# lab1.net
KiCad netlist of a schematic drawn in EAGLE
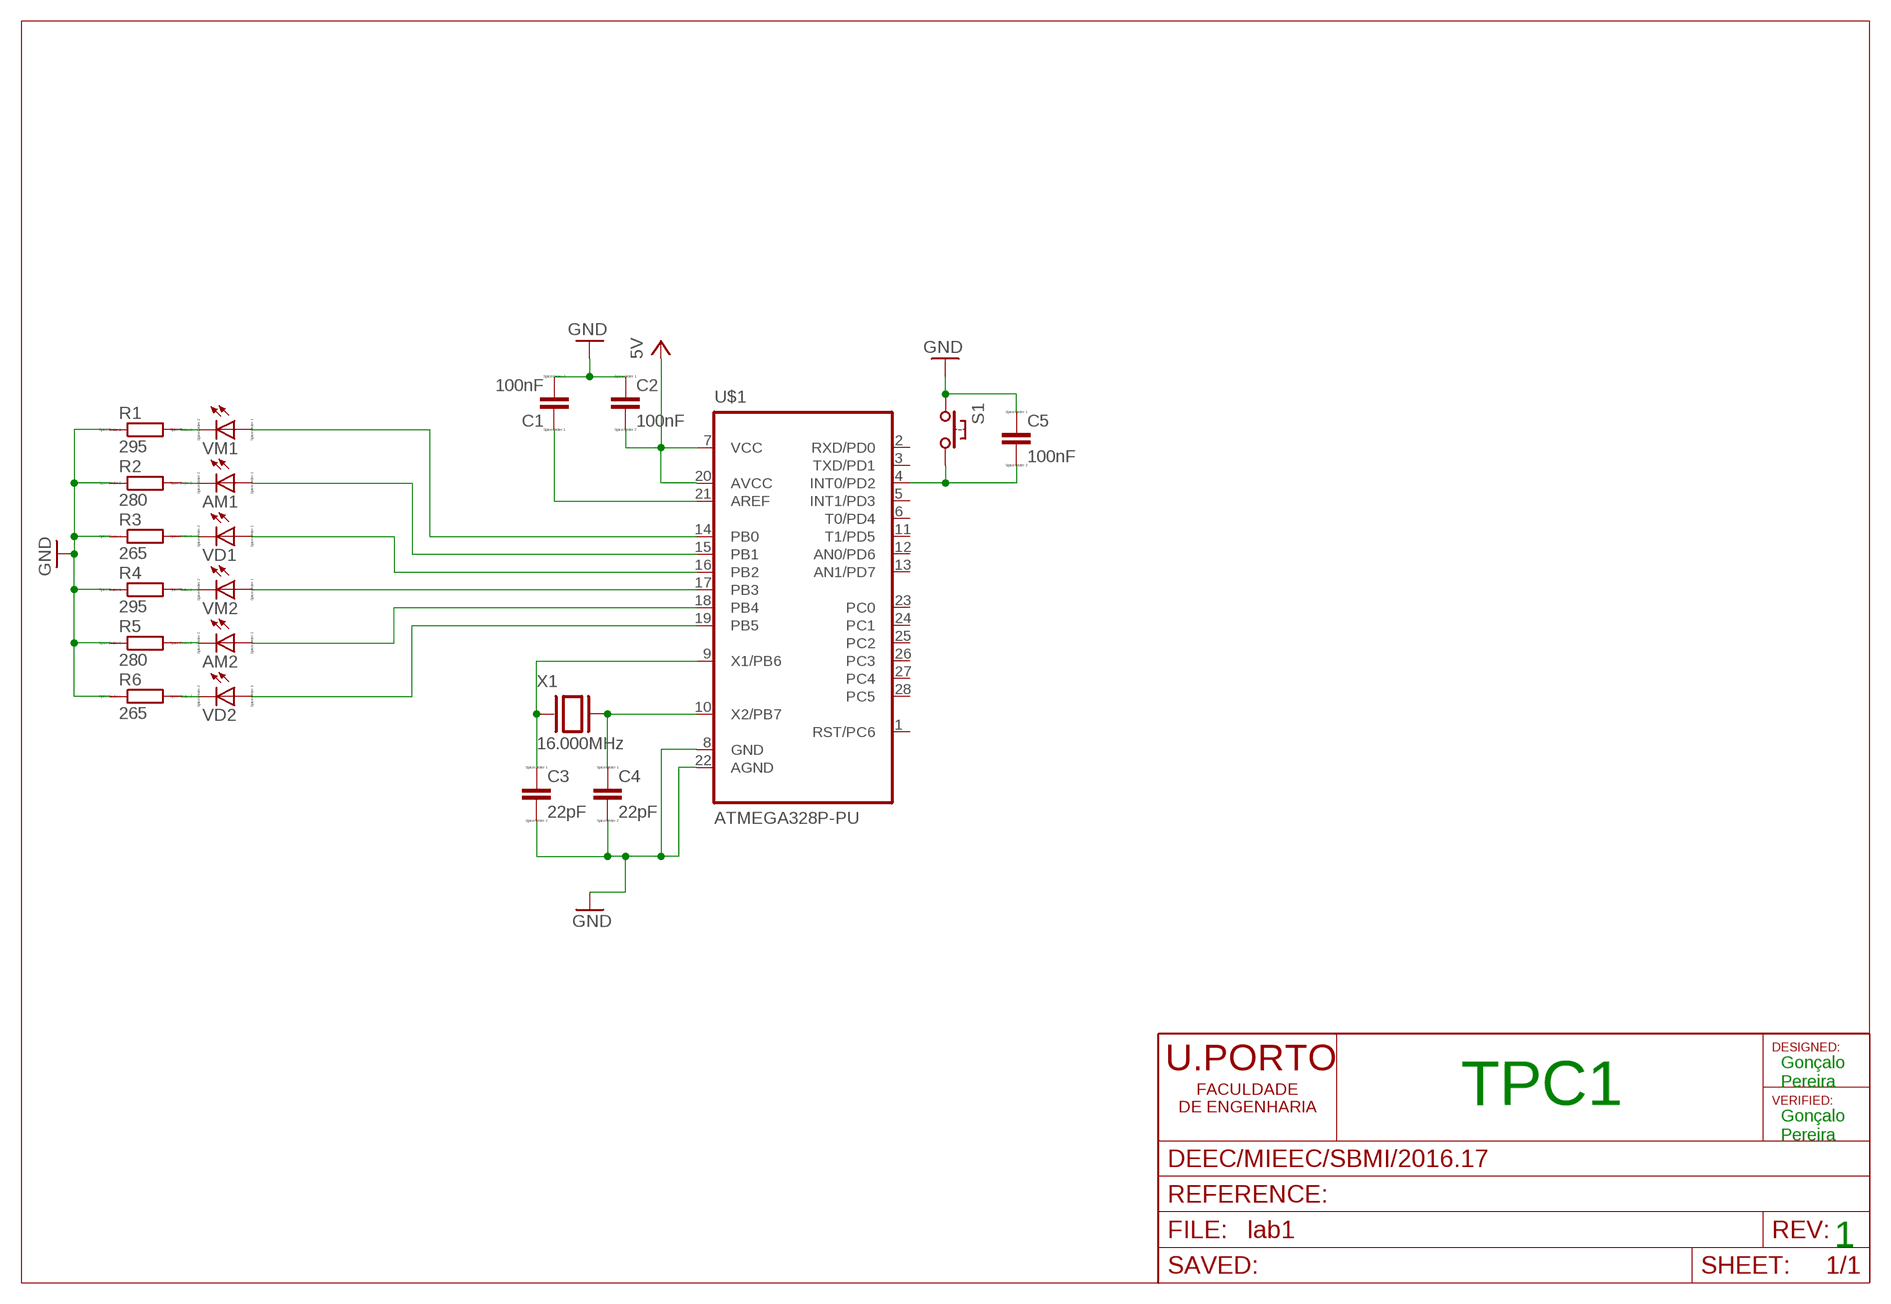
[diagram p0: schematic, sheet 1]

(export (version "E")
  (design (tool "Eeschema 10.0.6"))
  (components
    (comp (ref "AM1")
      (value "LED_ELD260")
      (footprint "eagle-import:LED_LD260")
      (libsource (lib "eagle-import") (part "LED_ELD260"))
    )
    (comp (ref "AM2")
      (value "LED_ELD260")
      (footprint "eagle-import:LED_LD260")
      (libsource (lib "eagle-import") (part "LED_ELD260"))
    )
    (comp (ref "C1")
      (value "100nF")
      (footprint "eagle-import:C0805")
      (libsource (lib "eagle-import") (part "C"))
    )
    (comp (ref "C2")
      (value "100nF")
      (footprint "eagle-import:C0805")
      (libsource (lib "eagle-import") (part "C"))
    )
    (comp (ref "C3")
      (value "22pF")
      (footprint "eagle-import:C0805")
      (libsource (lib "eagle-import") (part "C"))
    )
    (comp (ref "C4")
      (value "22pF")
      (footprint "eagle-import:C0805")
      (libsource (lib "eagle-import") (part "C"))
    )
    (comp (ref "C5")
      (value "100nF")
      (footprint "eagle-import:C0805")
      (libsource (lib "eagle-import") (part "C"))
    )
    (comp (ref "R1")
      (value "295")
      (footprint "eagle-import:0204_7")
      (libsource (lib "eagle-import") (part "R0204/7"))
    )
    (comp (ref "R2")
      (value "280")
      (footprint "eagle-import:0204_7")
      (libsource (lib "eagle-import") (part "R0204/7"))
    )
    (comp (ref "R3")
      (value "265")
      (footprint "eagle-import:0204_7")
      (libsource (lib "eagle-import") (part "R0204/7"))
    )
    (comp (ref "R4")
      (value "295")
      (footprint "eagle-import:0204_7")
      (libsource (lib "eagle-import") (part "R0204/7"))
    )
    (comp (ref "R5")
      (value "280")
      (footprint "eagle-import:0204_7")
      (libsource (lib "eagle-import") (part "R0204/7"))
    )
    (comp (ref "R6")
      (value "265")
      (footprint "eagle-import:0204_7")
      (libsource (lib "eagle-import") (part "R0204/7"))
    )
    (comp (ref "S1")
      (value "PBUTTON")
      (footprint "eagle-import:B3F-31XX")
      (fields (field (name "MPN") "B3F-3100"))
      (libsource (lib "eagle-import") (part "PBUTTON"))
    )
    (comp (ref "U$1")
      (value "ATMEGA328P-PU")
      (footprint "eagle-import:PDIP28")
      (libsource (lib "eagle-import") (part "ATMEGA328P-PU"))
    )
    (comp (ref "VD1")
      (value "LED_ELD260")
      (footprint "eagle-import:LED_LD260")
      (libsource (lib "eagle-import") (part "LED_ELD260"))
    )
    (comp (ref "VD2")
      (value "LED_ELD260")
      (footprint "eagle-import:LED_LD260")
      (libsource (lib "eagle-import") (part "LED_ELD260"))
    )
    (comp (ref "VM1")
      (value "LED_ELD260")
      (footprint "eagle-import:LED_LD260")
      (libsource (lib "eagle-import") (part "LED_ELD260"))
    )
    (comp (ref "VM2")
      (value "LED_ELD260")
      (footprint "eagle-import:LED_LD260")
      (libsource (lib "eagle-import") (part "LED_ELD260"))
    )
    (comp (ref "X1")
      (value "16.000MHz")
      (footprint "eagle-import:Q")
      (libsource (lib "eagle-import") (part "XTAL"))
    )
  )
  (nets
    (net (code "1") (name "5V") (class "Default")
      (node (ref "C2") (pin "2") (pinfunction "2_2") (pintype "passive"))
      (node (ref "U$1") (pin "20") (pinfunction "AVCC_20") (pintype "bidirectional"))
      (node (ref "U$1") (pin "7") (pinfunction "VCC_7") (pintype "bidirectional"))
    )
    (net (code "2") (name "GND") (class "Default")
      (node (ref "C1") (pin "2") (pinfunction "2_2") (pintype "passive"))
      (node (ref "C2") (pin "1") (pinfunction "1_1") (pintype "passive"))
      (node (ref "C3") (pin "2") (pinfunction "2_2") (pintype "passive"))
      (node (ref "C4") (pin "2") (pinfunction "2_2") (pintype "passive"))
      (node (ref "C5") (pin "1") (pinfunction "1_1") (pintype "passive"))
      (node (ref "R1") (pin "1") (pinfunction "1_1") (pintype "passive"))
      (node (ref "R2") (pin "1") (pinfunction "1_1") (pintype "passive"))
      (node (ref "R3") (pin "1") (pinfunction "1_1") (pintype "passive"))
      (node (ref "R4") (pin "1") (pinfunction "1_1") (pintype "passive"))
      (node (ref "R5") (pin "1") (pinfunction "1_1") (pintype "passive"))
      (node (ref "R6") (pin "1") (pinfunction "1_1") (pintype "passive"))
      (node (ref "S1") (pin "1") (pinfunction "P_1") (pintype "passive"))
      (node (ref "U$1") (pin "22") (pinfunction "AGND_22") (pintype "bidirectional"))
      (node (ref "U$1") (pin "8") (pinfunction "GND_8") (pintype "bidirectional"))
    )
    (net (code "3") (name "Net-(AM1-C)") (class "Default")
      (node (ref "AM1") (pin "K") (pinfunction "C_K") (pintype "passive"))
      (node (ref "R2") (pin "2") (pinfunction "2_2") (pintype "passive"))
    )
    (net (code "4") (name "Net-(AM2-C)") (class "Default")
      (node (ref "AM2") (pin "K") (pinfunction "C_K") (pintype "passive"))
      (node (ref "R5") (pin "2") (pinfunction "2_2") (pintype "passive"))
    )
    (net (code "5") (name "Net-(S1-S)") (class "Default")
      (node (ref "C5") (pin "2") (pinfunction "2_2") (pintype "passive"))
      (node (ref "S1") (pin "2") (pinfunction "S_2") (pintype "passive"))
      (node (ref "U$1") (pin "4") (pinfunction "INT0/PD2_4") (pintype "bidirectional"))
    )
    (net (code "6") (name "Net-(U$1-AREF)") (class "Default")
      (node (ref "C1") (pin "1") (pinfunction "1_1") (pintype "passive"))
      (node (ref "U$1") (pin "21") (pinfunction "AREF_21") (pintype "bidirectional"))
    )
    (net (code "7") (name "Net-(U$1-PB0)") (class "Default")
      (node (ref "U$1") (pin "14") (pinfunction "PB0_14") (pintype "bidirectional"))
      (node (ref "VM1") (pin "A") (pinfunction "A_A") (pintype "passive"))
    )
    (net (code "8") (name "Net-(U$1-PB1)") (class "Default")
      (node (ref "AM1") (pin "A") (pinfunction "A_A") (pintype "passive"))
      (node (ref "U$1") (pin "15") (pinfunction "PB1_15") (pintype "bidirectional"))
    )
    (net (code "9") (name "Net-(U$1-PB2)") (class "Default")
      (node (ref "U$1") (pin "16") (pinfunction "PB2_16") (pintype "bidirectional"))
      (node (ref "VD1") (pin "A") (pinfunction "A_A") (pintype "passive"))
    )
    (net (code "10") (name "Net-(U$1-PB3)") (class "Default")
      (node (ref "U$1") (pin "17") (pinfunction "PB3_17") (pintype "bidirectional"))
      (node (ref "VM2") (pin "A") (pinfunction "A_A") (pintype "passive"))
    )
    (net (code "11") (name "Net-(U$1-PB4)") (class "Default")
      (node (ref "AM2") (pin "A") (pinfunction "A_A") (pintype "passive"))
      (node (ref "U$1") (pin "18") (pinfunction "PB4_18") (pintype "bidirectional"))
    )
    (net (code "12") (name "Net-(U$1-PB5)") (class "Default")
      (node (ref "U$1") (pin "19") (pinfunction "PB5_19") (pintype "bidirectional"))
      (node (ref "VD2") (pin "A") (pinfunction "A_A") (pintype "passive"))
    )
    (net (code "13") (name "Net-(U$1-X1{slash}PB6)") (class "Default")
      (node (ref "C3") (pin "1") (pinfunction "1_1") (pintype "passive"))
      (node (ref "U$1") (pin "9") (pinfunction "X1/PB6_9") (pintype "bidirectional"))
      (node (ref "X1") (pin "2") (pinfunction "1_2") (pintype "passive"))
    )
    (net (code "14") (name "Net-(U$1-X2{slash}PB7)") (class "Default")
      (node (ref "C4") (pin "1") (pinfunction "1_1") (pintype "passive"))
      (node (ref "U$1") (pin "10") (pinfunction "X2/PB7_10") (pintype "bidirectional"))
      (node (ref "X1") (pin "1") (pinfunction "2_1") (pintype "passive"))
    )
    (net (code "15") (name "Net-(VD1-C)") (class "Default")
      (node (ref "R3") (pin "2") (pinfunction "2_2") (pintype "passive"))
      (node (ref "VD1") (pin "K") (pinfunction "C_K") (pintype "passive"))
    )
    (net (code "16") (name "Net-(VD2-C)") (class "Default")
      (node (ref "R6") (pin "2") (pinfunction "2_2") (pintype "passive"))
      (node (ref "VD2") (pin "K") (pinfunction "C_K") (pintype "passive"))
    )
    (net (code "17") (name "Net-(VM1-C)") (class "Default")
      (node (ref "R1") (pin "2") (pinfunction "2_2") (pintype "passive"))
      (node (ref "VM1") (pin "K") (pinfunction "C_K") (pintype "passive"))
    )
    (net (code "18") (name "Net-(VM2-C)") (class "Default")
      (node (ref "R4") (pin "2") (pinfunction "2_2") (pintype "passive"))
      (node (ref "VM2") (pin "K") (pinfunction "C_K") (pintype "passive"))
    )
    (net (code "19") (name "unconnected-(U$1-AN0{slash}PD6-Pad12)") (class "Default")
      (node (ref "U$1") (pin "12") (pinfunction "AN0/PD6_12") (pintype "bidirectional"))
    )
    (net (code "20") (name "unconnected-(U$1-AN1{slash}PD7-Pad13)") (class "Default")
      (node (ref "U$1") (pin "13") (pinfunction "AN1/PD7_13") (pintype "bidirectional"))
    )
    (net (code "21") (name "unconnected-(U$1-INT1{slash}PD3-Pad5)") (class "Default")
      (node (ref "U$1") (pin "5") (pinfunction "INT1/PD3_5") (pintype "bidirectional"))
    )
    (net (code "22") (name "unconnected-(U$1-PC0-Pad23)") (class "Default")
      (node (ref "U$1") (pin "23") (pinfunction "PC0_23") (pintype "bidirectional"))
    )
    (net (code "23") (name "unconnected-(U$1-PC1-Pad24)") (class "Default")
      (node (ref "U$1") (pin "24") (pinfunction "PC1_24") (pintype "bidirectional"))
    )
    (net (code "24") (name "unconnected-(U$1-PC2-Pad25)") (class "Default")
      (node (ref "U$1") (pin "25") (pinfunction "PC2_25") (pintype "bidirectional"))
    )
    (net (code "25") (name "unconnected-(U$1-PC3-Pad26)") (class "Default")
      (node (ref "U$1") (pin "26") (pinfunction "PC3_26") (pintype "bidirectional"))
    )
    (net (code "26") (name "unconnected-(U$1-PC4-Pad27)") (class "Default")
      (node (ref "U$1") (pin "27") (pinfunction "PC4_27") (pintype "bidirectional"))
    )
    (net (code "27") (name "unconnected-(U$1-PC5-Pad28)") (class "Default")
      (node (ref "U$1") (pin "28") (pinfunction "PC5_28") (pintype "bidirectional"))
    )
    (net (code "28") (name "unconnected-(U$1-RST{slash}PC6-Pad1)") (class "Default")
      (node (ref "U$1") (pin "1") (pinfunction "RST/PC6_1") (pintype "bidirectional"))
    )
    (net (code "29") (name "unconnected-(U$1-RXD{slash}PD0-Pad2)") (class "Default")
      (node (ref "U$1") (pin "2") (pinfunction "RXD/PD0_2") (pintype "bidirectional"))
    )
    (net (code "30") (name "unconnected-(U$1-T0{slash}PD4-Pad6)") (class "Default")
      (node (ref "U$1") (pin "6") (pinfunction "T0/PD4_6") (pintype "bidirectional"))
    )
    (net (code "31") (name "unconnected-(U$1-T1{slash}PD5-Pad11)") (class "Default")
      (node (ref "U$1") (pin "11") (pinfunction "T1/PD5_11") (pintype "bidirectional"))
    )
    (net (code "32") (name "unconnected-(U$1-TXD{slash}PD1-Pad3)") (class "Default")
      (node (ref "U$1") (pin "3") (pinfunction "TXD/PD1_3") (pintype "bidirectional"))
    )
  )
)
